# JEMA.net
KiCad netlist of a schematic drawn in EAGLE
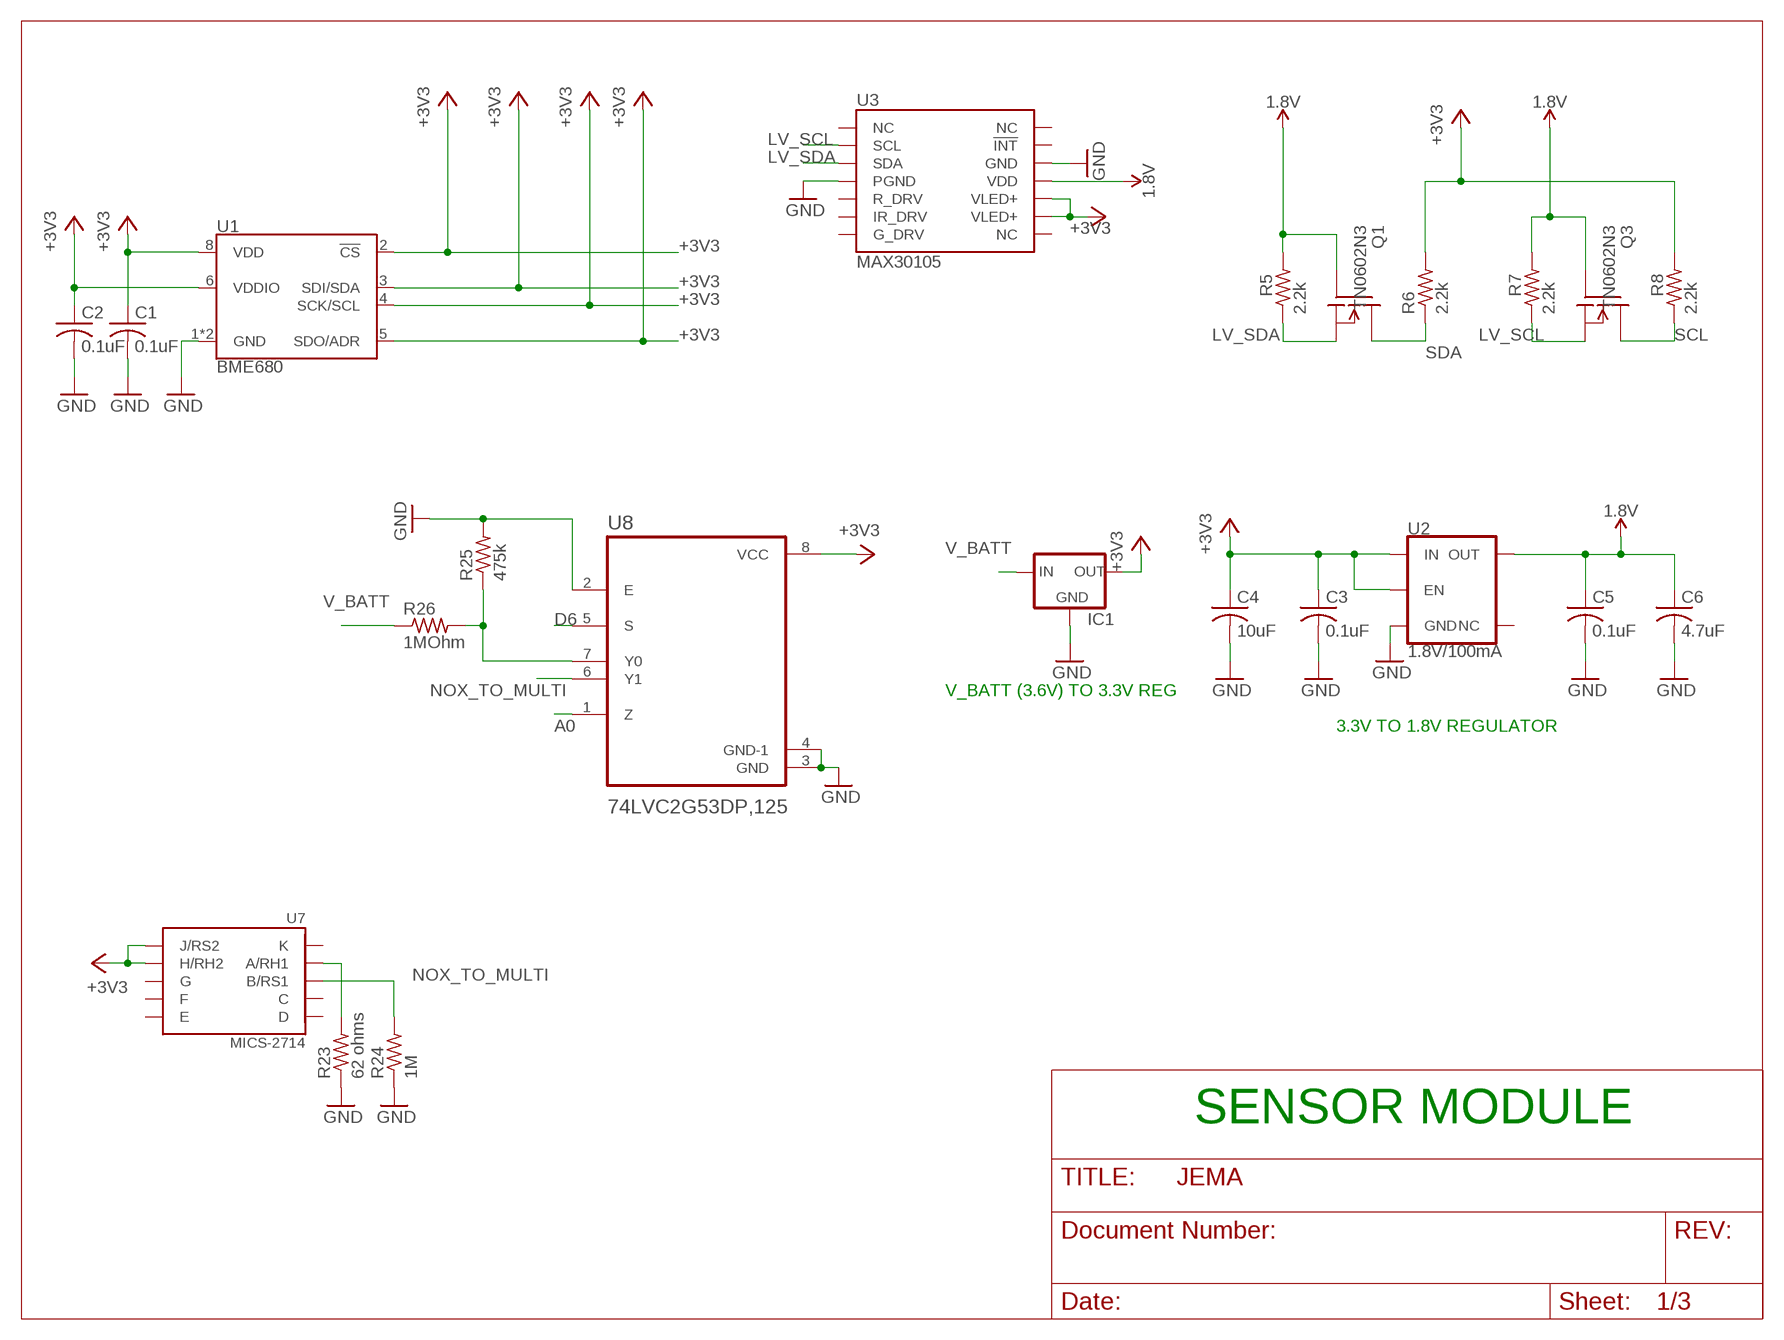
[diagram p0: schematic, sheet 1]
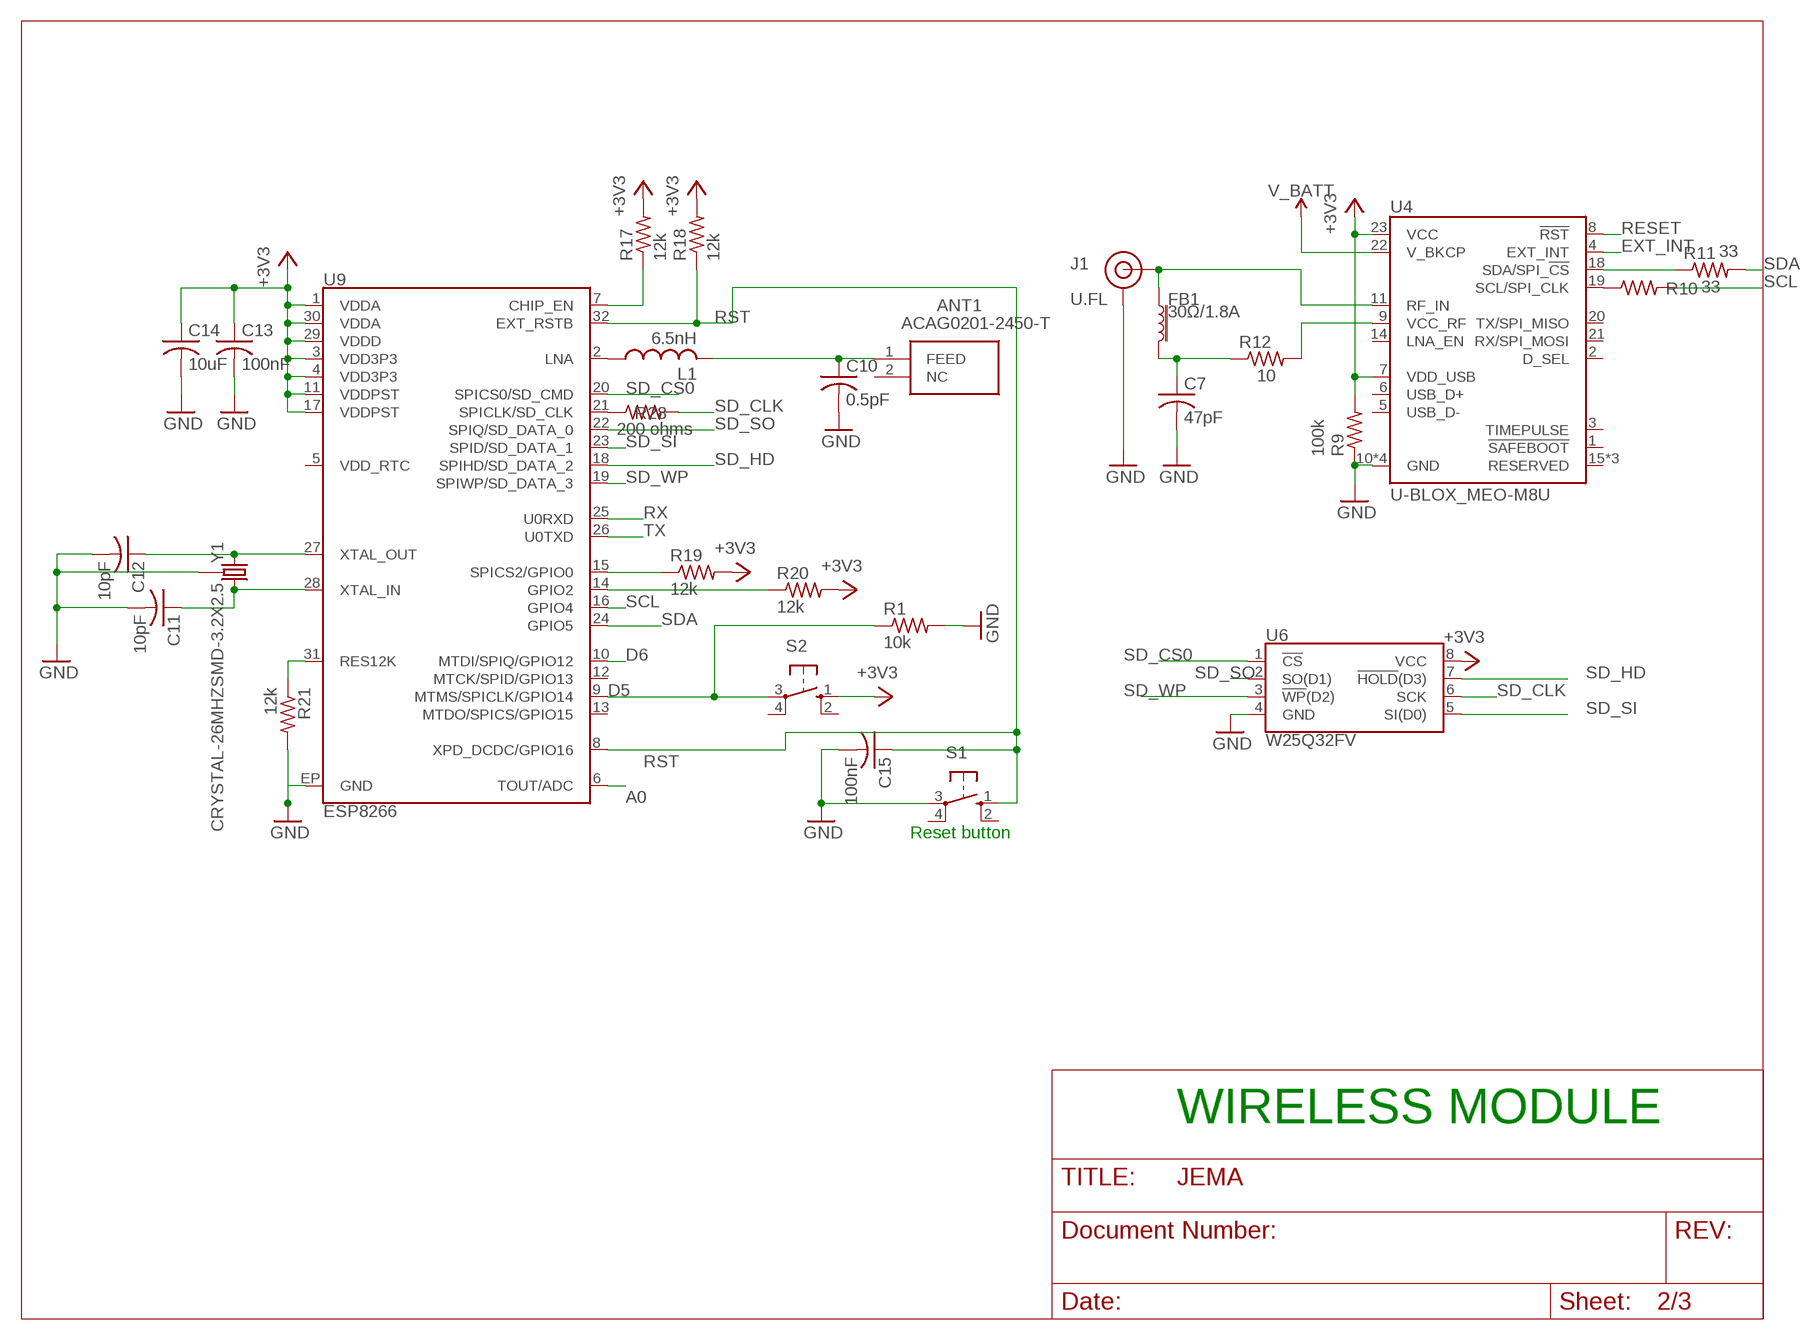
[diagram p1: schematic, sheet 2]
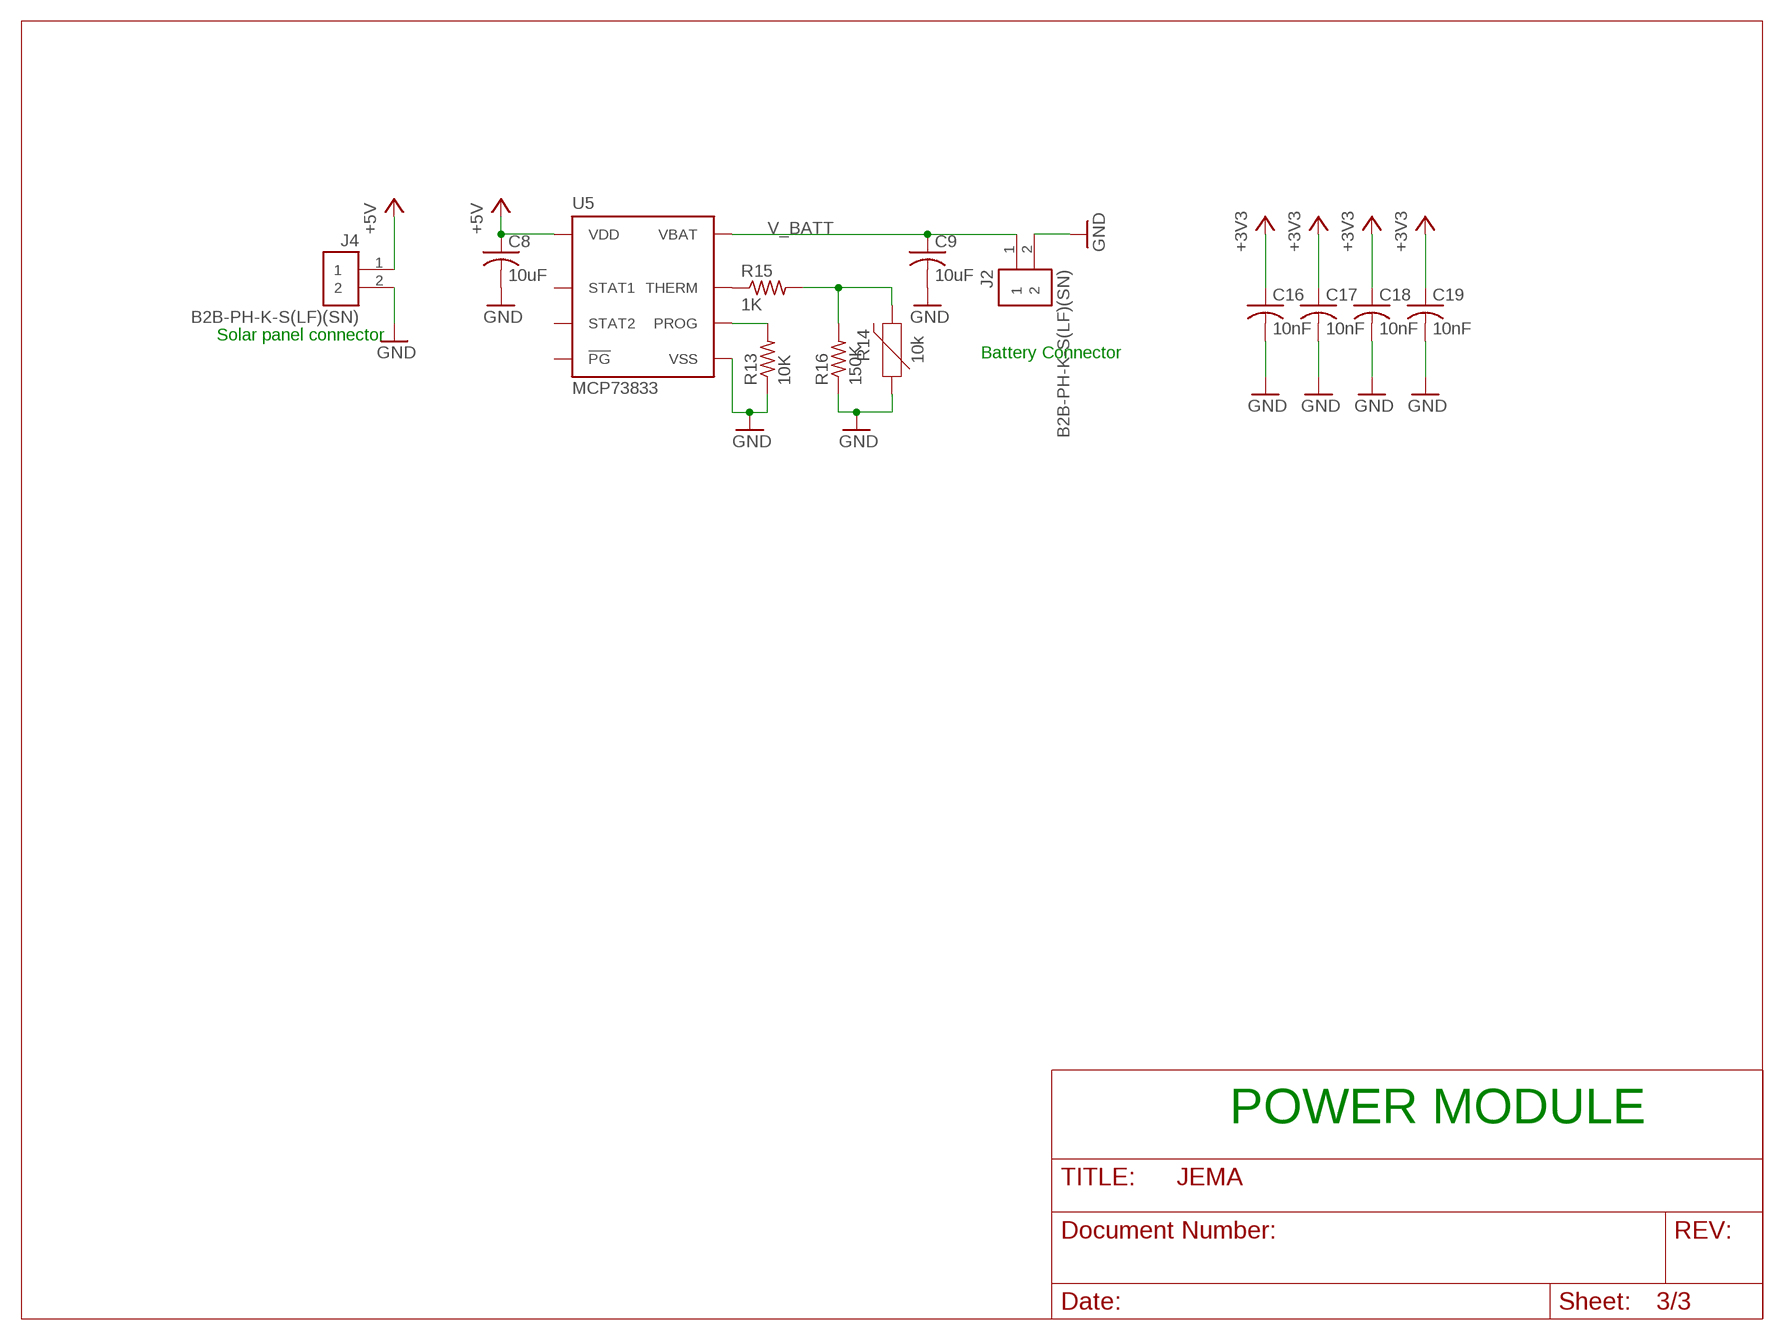
[diagram p2: schematic, sheet 3]

(export (version "E")
  (design (tool "Eeschema 10.0.6"))
  (components
    (comp (ref "C8")
      (value "10uF")
      (footprint "eagle-import:C0805")
      (libsource (lib "eagle-import") (part "C-USC0805"))
    )
    (comp (ref "C9")
      (value "10uF")
      (footprint "eagle-import:C0805")
      (libsource (lib "eagle-import") (part "C-USC0805"))
    )
    (comp (ref "C16")
      (value "10nF")
      (footprint "eagle-import:C0805")
      (libsource (lib "eagle-import") (part "C-USC0805"))
    )
    (comp (ref "C17")
      (value "10nF")
      (footprint "eagle-import:C0805")
      (libsource (lib "eagle-import") (part "C-USC0805"))
    )
    (comp (ref "C18")
      (value "10nF")
      (footprint "eagle-import:C0805")
      (libsource (lib "eagle-import") (part "C-USC0805"))
    )
    (comp (ref "C19")
      (value "10nF")
      (footprint "eagle-import:C0805")
      (libsource (lib "eagle-import") (part "C-USC0805"))
    )
    (comp (ref "J2")
      (value "B2B-PH-K-S(LF)(SN)")
      (footprint "eagle-import:JST_B2B-PH-K-S(LF)(SN)")
      (fields (field (name "MF") "JST Sales"))
      (libsource (lib "eagle-import") (part "B2B-PH-K-S(LF)(SN)"))
    )
    (comp (ref "J4")
      (value "B2B-PH-K-S(LF)(SN)")
      (footprint "eagle-import:JST_B2B-PH-K-S(LF)(SN)")
      (fields (field (name "MF") "JST Sales"))
      (libsource (lib "eagle-import") (part "B2B-PH-K-S(LF)(SN)"))
    )
    (comp (ref "R13")
      (value "10K")
      (footprint "eagle-import:R0805")
      (libsource (lib "eagle-import") (part "R-US_R0805"))
    )
    (comp (ref "R14")
      (value "10k")
      (footprint "eagle-import:0603")
      (libsource (lib "eagle-import") (part "NTC-THERMISTOR-0603"))
    )
    (comp (ref "R15")
      (value "1K")
      (footprint "eagle-import:R0805")
      (libsource (lib "eagle-import") (part "R-US_R0805"))
    )
    (comp (ref "R16")
      (value "150K")
      (footprint "eagle-import:R0805")
      (libsource (lib "eagle-import") (part "R-US_R0805"))
    )
    (comp (ref "U5")
      (value "MCP73833")
      (footprint "eagle-import:DFN-10")
      (libsource (lib "eagle-import") (part "MCP73833"))
    )
    (comp (ref "ANT1")
      (value "ACAG0201-2450-T")
      (footprint "eagle-import:ANTC2012X70N")
      (fields (field (name "MOUSER_PART_NUMBER") "815-G0201-2450-T"))
      (libsource (lib "eagle-import") (part "ACAG0201-2450-T"))
    )
    (comp (ref "C7")
      (value "47pF")
      (footprint "eagle-import:C0805")
      (libsource (lib "eagle-import") (part "C-USC0805"))
    )
    (comp (ref "C10")
      (value "0.5pF")
      (footprint "eagle-import:C0805")
      (libsource (lib "eagle-import") (part "C-USC0805"))
    )
    (comp (ref "C11")
      (value "10pF")
      (footprint "eagle-import:C0805")
      (libsource (lib "eagle-import") (part "C-USC0805"))
    )
    (comp (ref "C12")
      (value "10pF")
      (footprint "eagle-import:C0805")
      (libsource (lib "eagle-import") (part "C-USC0805"))
    )
    (comp (ref "C13")
      (value "100nF")
      (footprint "eagle-import:C0805")
      (libsource (lib "eagle-import") (part "C-USC0805"))
    )
    (comp (ref "C14")
      (value "10uF")
      (footprint "eagle-import:C0805")
      (libsource (lib "eagle-import") (part "C-USC0805"))
    )
    (comp (ref "C15")
      (value "100nF")
      (footprint "eagle-import:C0805")
      (libsource (lib "eagle-import") (part "C-USC0805"))
    )
    (comp (ref "FB1")
      (value "30Ω/1.8A")
      (footprint "eagle-import:0603")
      (libsource (lib "eagle-import") (part "FERRITE_BEAD-0603"))
    )
    (comp (ref "J1")
      (value "U.FL")
      (footprint "eagle-import:U.FL")
      (libsource (lib "eagle-import") (part "U.FL2PIN"))
    )
    (comp (ref "L1")
      (value "6.5nH")
      (footprint "eagle-import:L3225M")
      (libsource (lib "eagle-import") (part "L-USL3225M"))
    )
    (comp (ref "R1")
      (value "10k")
      (footprint "eagle-import:R0805")
      (libsource (lib "eagle-import") (part "R-US_R0805"))
    )
    (comp (ref "R9")
      (value "100k")
      (footprint "eagle-import:R0805")
      (libsource (lib "eagle-import") (part "R-US_R0805"))
    )
    (comp (ref "R10")
      (value "33")
      (footprint "eagle-import:R0805")
      (libsource (lib "eagle-import") (part "R-US_R0805"))
    )
    (comp (ref "R11")
      (value "33")
      (footprint "eagle-import:R0805")
      (libsource (lib "eagle-import") (part "R-US_R0805"))
    )
    (comp (ref "R12")
      (value "10")
      (footprint "eagle-import:R0805")
      (libsource (lib "eagle-import") (part "R-US_R0805"))
    )
    (comp (ref "R17")
      (value "12k")
      (footprint "eagle-import:M0805")
      (libsource (lib "eagle-import") (part "R-US_M0805"))
    )
    (comp (ref "R18")
      (value "12k")
      (footprint "eagle-import:M0805")
      (libsource (lib "eagle-import") (part "R-US_M0805"))
    )
    (comp (ref "R19")
      (value "12k")
      (footprint "eagle-import:M0805")
      (libsource (lib "eagle-import") (part "R-US_M0805"))
    )
    (comp (ref "R20")
      (value "12k")
      (footprint "eagle-import:M0805")
      (libsource (lib "eagle-import") (part "R-US_M0805"))
    )
    (comp (ref "R21")
      (value "12k")
      (footprint "eagle-import:M0805")
      (libsource (lib "eagle-import") (part "R-US_M0805"))
    )
    (comp (ref "R28")
      (value "200 ohms")
      (footprint "eagle-import:R0805")
      (libsource (lib "eagle-import") (part "R-US_R0805"))
    )
    (comp (ref "S1")
      (value "10-XX")
      (footprint "eagle-import:B3F-10XX")
      (fields (field (name "MPN") "B3F-1000"))
      (libsource (lib "eagle-import") (part "10-XX"))
    )
    (comp (ref "S2")
      (value "10-XX")
      (footprint "eagle-import:B3F-10XX")
      (fields (field (name "MPN") "B3F-1000"))
      (libsource (lib "eagle-import") (part "10-XX"))
    )
    (comp (ref "U4")
      (value "U-BLOX_MEO-M8U")
      (footprint "eagle-import:NEO-M9N_M8T_M8U")
      (libsource (lib "eagle-import") (part "U-BLOX_MEO-M8U"))
    )
    (comp (ref "U6")
      (value "W25Q32FV")
      (footprint "eagle-import:SOIC-8")
      (libsource (lib "eagle-import") (part "W25Q32FVSS"))
    )
    (comp (ref "U9")
      (value "ESP8266")
      (footprint "eagle-import:QFN32-5X5MM")
      (libsource (lib "eagle-import") (part "ESP8266"))
    )
    (comp (ref "Y1")
      (value "CRYSTAL-26MHZSMD-3.2X2.5")
      (footprint "eagle-import:CRYSTAL-SMD-3.2X2.5MM")
      (libsource (lib "eagle-import") (part "CRYSTAL-26MHZSMD-3.2X2.5"))
    )
    (comp (ref "C1")
      (value "0.1uF")
      (footprint "eagle-import:C0805")
      (libsource (lib "eagle-import") (part "C-USC0805"))
    )
    (comp (ref "C2")
      (value "0.1uF")
      (footprint "eagle-import:C0805")
      (libsource (lib "eagle-import") (part "C-USC0805"))
    )
    (comp (ref "C3")
      (value "0.1uF")
      (footprint "eagle-import:C0805")
      (libsource (lib "eagle-import") (part "C-USC0805"))
    )
    (comp (ref "C4")
      (value "10uF")
      (footprint "eagle-import:C0805")
      (libsource (lib "eagle-import") (part "C-USC0805"))
    )
    (comp (ref "C5")
      (value "0.1uF")
      (footprint "eagle-import:C0805")
      (libsource (lib "eagle-import") (part "C-USC0805"))
    )
    (comp (ref "C6")
      (value "4.7uF")
      (footprint "eagle-import:C0805")
      (libsource (lib "eagle-import") (part "C-USC0805"))
    )
    (comp (ref "IC1")
      (value "MCP1700TRI")
      (footprint "eagle-import:TO92")
      (libsource (lib "eagle-import") (part "MCP1700TRI"))
    )
    (comp (ref "Q1")
      (value "TN0602N3")
      (footprint "eagle-import:TO-92")
      (libsource (lib "eagle-import") (part "TN0602N3"))
    )
    (comp (ref "Q3")
      (value "TN0602N3")
      (footprint "eagle-import:TO-92")
      (libsource (lib "eagle-import") (part "TN0602N3"))
    )
    (comp (ref "R5")
      (value "2.2k")
      (footprint "eagle-import:R0805")
      (libsource (lib "eagle-import") (part "R-US_R0805"))
    )
    (comp (ref "R6")
      (value "2.2k")
      (footprint "eagle-import:R0805")
      (libsource (lib "eagle-import") (part "R-US_R0805"))
    )
    (comp (ref "R7")
      (value "2.2k")
      (footprint "eagle-import:R0805")
      (libsource (lib "eagle-import") (part "R-US_R0805"))
    )
    (comp (ref "R8")
      (value "2.2k")
      (footprint "eagle-import:R0805")
      (libsource (lib "eagle-import") (part "R-US_R0805"))
    )
    (comp (ref "R23")
      (value "62 ohms")
      (footprint "eagle-import:M0805")
      (libsource (lib "eagle-import") (part "R-US_M0805"))
    )
    (comp (ref "R24")
      (value "1M")
      (footprint "eagle-import:M0805")
      (libsource (lib "eagle-import") (part "R-US_M0805"))
    )
    (comp (ref "R25")
      (value "475k")
      (footprint "eagle-import:M0805")
      (libsource (lib "eagle-import") (part "R-US_M0805"))
    )
    (comp (ref "R26")
      (value "1MOhm")
      (footprint "eagle-import:M0805")
      (libsource (lib "eagle-import") (part "R-US_M0805"))
    )
    (comp (ref "U1")
      (value "BME680")
      (footprint "eagle-import:LGA3.0X3.0")
      (libsource (lib "eagle-import") (part "BME680-LGA"))
    )
    (comp (ref "U2")
      (value "1.8V/100mA")
      (footprint "eagle-import:SC70")
      (libsource (lib "eagle-import") (part "V_REG_SP6214-1.8V"))
    )
    (comp (ref "U3")
      (value "MAX30105")
      (footprint "eagle-import:OLGA-14")
      (libsource (lib "eagle-import") (part "MAX3010X-30105"))
    )
    (comp (ref "U7")
      (value "MICS-2714")
      (footprint "eagle-import:MICS-SMD10")
      (fields (field (name "MF") "SGX Sensortech"))
      (libsource (lib "eagle-import") (part "MICS-2714"))
    )
    (comp (ref "U8")
      (value "74LVC2G53DP,125")
      (footprint "eagle-import:SOP65P490X110-8N")
      (fields (field (name "MF") "Nexperia USA"))
      (libsource (lib "eagle-import") (part "74LVC2G53DP,125"))
    )
  )
  (nets
    (net (code "1") (name "+3V3") (class "Default")
      (node (ref "C1") (pin "1") (pinfunction "1_1") (pintype "passive"))
      (node (ref "C13") (pin "1") (pinfunction "1_1") (pintype "passive"))
      (node (ref "C14") (pin "1") (pinfunction "1_1") (pintype "passive"))
      (node (ref "C16") (pin "1") (pinfunction "1_1") (pintype "passive"))
      (node (ref "C17") (pin "1") (pinfunction "1_1") (pintype "passive"))
      (node (ref "C18") (pin "1") (pinfunction "1_1") (pintype "passive"))
      (node (ref "C19") (pin "1") (pinfunction "1_1") (pintype "passive"))
      (node (ref "C2") (pin "1") (pinfunction "1_1") (pintype "passive"))
      (node (ref "C3") (pin "1") (pinfunction "1_1") (pintype "passive"))
      (node (ref "C4") (pin "1") (pinfunction "1_1") (pintype "passive"))
      (node (ref "IC1") (pin "3") (pinfunction "OUT_3") (pintype "passive"))
      (node (ref "R17") (pin "2") (pinfunction "2_2") (pintype "passive"))
      (node (ref "R18") (pin "2") (pinfunction "2_2") (pintype "passive"))
      (node (ref "R19") (pin "2") (pinfunction "2_2") (pintype "passive"))
      (node (ref "R20") (pin "2") (pinfunction "2_2") (pintype "passive"))
      (node (ref "R6") (pin "2") (pinfunction "2_2") (pintype "passive"))
      (node (ref "R8") (pin "2") (pinfunction "2_2") (pintype "passive"))
      (node (ref "R9") (pin "2") (pinfunction "2_2") (pintype "passive"))
      (node (ref "S2") (pin "1") (pinfunction "S_1") (pintype "passive"))
      (node (ref "U1") (pin "2") (pinfunction "~{CS}_2") (pintype "bidirectional"))
      (node (ref "U1") (pin "3") (pinfunction "SDI/SDA_3") (pintype "bidirectional"))
      (node (ref "U1") (pin "4") (pinfunction "SCK/SCL_4") (pintype "bidirectional"))
      (node (ref "U1") (pin "5") (pinfunction "SDO/ADR_5") (pintype "bidirectional"))
      (node (ref "U1") (pin "6") (pinfunction "VDDIO_6") (pintype "bidirectional"))
      (node (ref "U1") (pin "8") (pinfunction "VDD_8") (pintype "bidirectional"))
      (node (ref "U2") (pin "1") (pinfunction "IN_1") (pintype "input"))
      (node (ref "U2") (pin "3") (pinfunction "EN_3") (pintype "input"))
      (node (ref "U3") (pin "10") (pinfunction "VLED+_10") (pintype "bidirectional"))
      (node (ref "U3") (pin "9") (pinfunction "VLED+_9") (pintype "bidirectional"))
      (node (ref "U4") (pin "23") (pinfunction "VCC_23") (pintype "bidirectional"))
      (node (ref "U4") (pin "7") (pinfunction "VDD_USB_7") (pintype "bidirectional"))
      (node (ref "U6") (pin "8") (pinfunction "VCC_8") (pintype "bidirectional"))
      (node (ref "U7") (pin "H") (pinfunction "H/RH2_H") (pintype "bidirectional"))
      (node (ref "U7") (pin "J") (pinfunction "J/RS2_J") (pintype "bidirectional"))
      (node (ref "U8") (pin "8") (pinfunction "VCC_8") (pintype "power_in"))
      (node (ref "U9") (pin "1") (pinfunction "VDDA_1") (pintype "bidirectional"))
      (node (ref "U9") (pin "11") (pinfunction "VDDPST_11") (pintype "bidirectional"))
      (node (ref "U9") (pin "17") (pinfunction "VDDPST_17") (pintype "bidirectional"))
      (node (ref "U9") (pin "29") (pinfunction "VDDD_29") (pintype "bidirectional"))
      (node (ref "U9") (pin "3") (pinfunction "VDD3P3_3") (pintype "bidirectional"))
      (node (ref "U9") (pin "30") (pinfunction "VDDA_30") (pintype "bidirectional"))
      (node (ref "U9") (pin "4") (pinfunction "VDD3P3_4") (pintype "bidirectional"))
    )
    (net (code "2") (name "+5V") (class "Default")
      (node (ref "C8") (pin "1") (pinfunction "1_1") (pintype "passive"))
      (node (ref "J4") (pin "1") (pinfunction "1_1") (pintype "passive"))
      (node (ref "U5") (pin "P$1") (pinfunction "VDD_P$1") (pintype "bidirectional"))
      (node (ref "U5") (pin "P$2") (pinfunction "VDD_P$2") (pintype "bidirectional"))
    )
    (net (code "3") (name "1.8V") (class "Default")
      (node (ref "C5") (pin "1") (pinfunction "1_1") (pintype "passive"))
      (node (ref "C6") (pin "1") (pinfunction "1_1") (pintype "passive"))
      (node (ref "Q1") (pin "2") (pinfunction "G_2") (pintype "passive"))
      (node (ref "Q3") (pin "2") (pinfunction "G_2") (pintype "passive"))
      (node (ref "R5") (pin "2") (pinfunction "2_2") (pintype "passive"))
      (node (ref "R7") (pin "2") (pinfunction "2_2") (pintype "passive"))
      (node (ref "U2") (pin "5") (pinfunction "OUT_5") (pintype "passive"))
      (node (ref "U3") (pin "11") (pinfunction "VDD_11") (pintype "bidirectional"))
    )
    (net (code "4") (name "A0") (class "Default")
      (node (ref "U8") (pin "1") (pinfunction "Z_1") (pintype "bidirectional"))
      (node (ref "U9") (pin "6") (pinfunction "TOUT/ADC_6") (pintype "bidirectional"))
    )
    (net (code "5") (name "D5") (class "Default")
      (node (ref "R1") (pin "1") (pinfunction "1_1") (pintype "passive"))
      (node (ref "S2") (pin "3") (pinfunction "P_3") (pintype "passive"))
      (node (ref "U9") (pin "9") (pinfunction "MTMS/SPICLK/GPIO14_9") (pintype "bidirectional"))
    )
    (net (code "6") (name "D6") (class "Default")
      (node (ref "U8") (pin "5") (pinfunction "S_5") (pintype "bidirectional"))
      (node (ref "U9") (pin "10") (pinfunction "MTDI/SPIQ/GPIO12_10") (pintype "bidirectional"))
    )
    (net (code "7") (name "EXT_INT") (class "Default")
      (node (ref "U4") (pin "4") (pinfunction "EXT_INT_4") (pintype "bidirectional"))
    )
    (net (code "8") (name "GND") (class "Default")
      (node (ref "C1") (pin "2") (pinfunction "2_2") (pintype "passive"))
      (node (ref "C10") (pin "2") (pinfunction "2_2") (pintype "passive"))
      (node (ref "C11") (pin "2") (pinfunction "2_2") (pintype "passive"))
      (node (ref "C12") (pin "2") (pinfunction "2_2") (pintype "passive"))
      (node (ref "C13") (pin "2") (pinfunction "2_2") (pintype "passive"))
      (node (ref "C14") (pin "2") (pinfunction "2_2") (pintype "passive"))
      (node (ref "C15") (pin "2") (pinfunction "2_2") (pintype "passive"))
      (node (ref "C16") (pin "2") (pinfunction "2_2") (pintype "passive"))
      (node (ref "C17") (pin "2") (pinfunction "2_2") (pintype "passive"))
      (node (ref "C18") (pin "2") (pinfunction "2_2") (pintype "passive"))
      (node (ref "C19") (pin "2") (pinfunction "2_2") (pintype "passive"))
      (node (ref "C2") (pin "2") (pinfunction "2_2") (pintype "passive"))
      (node (ref "C3") (pin "2") (pinfunction "2_2") (pintype "passive"))
      (node (ref "C4") (pin "2") (pinfunction "2_2") (pintype "passive"))
      (node (ref "C5") (pin "2") (pinfunction "2_2") (pintype "passive"))
      (node (ref "C6") (pin "2") (pinfunction "2_2") (pintype "passive"))
      (node (ref "C7") (pin "2") (pinfunction "2_2") (pintype "passive"))
      (node (ref "C8") (pin "2") (pinfunction "2_2") (pintype "passive"))
      (node (ref "C9") (pin "2") (pinfunction "2_2") (pintype "passive"))
      (node (ref "IC1") (pin "1") (pinfunction "GND_1") (pintype "input"))
      (node (ref "J1") (pin "1") (pinfunction "GND_1") (pintype "bidirectional"))
      (node (ref "J1") (pin "2") (pinfunction "GND_2") (pintype "bidirectional"))
      (node (ref "J2") (pin "2") (pinfunction "2_2") (pintype "passive"))
      (node (ref "J4") (pin "2") (pinfunction "2_2") (pintype "passive"))
      (node (ref "R1") (pin "2") (pinfunction "2_2") (pintype "passive"))
      (node (ref "R13") (pin "1") (pinfunction "1_1") (pintype "passive"))
      (node (ref "R14") (pin "1") (pinfunction "1_1") (pintype "bidirectional"))
      (node (ref "R16") (pin "1") (pinfunction "1_1") (pintype "passive"))
      (node (ref "R21") (pin "2") (pinfunction "2_2") (pintype "passive"))
      (node (ref "R23") (pin "1") (pinfunction "1_1") (pintype "passive"))
      (node (ref "R24") (pin "1") (pinfunction "1_1") (pintype "passive"))
      (node (ref "R25") (pin "2") (pinfunction "2_2") (pintype "passive"))
      (node (ref "R9") (pin "1") (pinfunction "1_1") (pintype "passive"))
      (node (ref "S1") (pin "3") (pinfunction "P_3") (pintype "passive"))
      (node (ref "U1") (pin "1") (pinfunction "GND_1") (pintype "bidirectional"))
      (node (ref "U1") (pin "7") (pinfunction "GND_7") (pintype "bidirectional"))
      (node (ref "U2") (pin "2") (pinfunction "GND_2") (pintype "input"))
      (node (ref "U3") (pin "12") (pinfunction "GND_12") (pintype "bidirectional"))
      (node (ref "U3") (pin "4") (pinfunction "PGND_4") (pintype "bidirectional"))
      (node (ref "U4") (pin "10") (pinfunction "GND_10") (pintype "bidirectional"))
      (node (ref "U4") (pin "12") (pinfunction "GND_12") (pintype "bidirectional"))
      (node (ref "U4") (pin "13") (pinfunction "GND_13") (pintype "bidirectional"))
      (node (ref "U4") (pin "24") (pinfunction "GND_24") (pintype "bidirectional"))
      (node (ref "U5") (pin "P$11") (pinfunction "VSS_P$11") (pintype "bidirectional"))
      (node (ref "U5") (pin "P$5") (pinfunction "VSS_P$5") (pintype "bidirectional"))
      (node (ref "U6") (pin "4") (pinfunction "GND_4") (pintype "bidirectional"))
      (node (ref "U8") (pin "2") (pinfunction "E_2") (pintype "bidirectional"))
      (node (ref "U8") (pin "3") (pinfunction "GND_3") (pintype "power_in"))
      (node (ref "U8") (pin "4") (pinfunction "GND-1_4") (pintype "power_in"))
      (node (ref "U9") (pin "EP") (pinfunction "GND_EP") (pintype "bidirectional"))
      (node (ref "Y1") (pin "2") (pinfunction "GND_2") (pintype "power_in"))
      (node (ref "Y1") (pin "4") (pinfunction "GND_4") (pintype "power_in"))
    )
    (net (code "9") (name "LV_SCL") (class "Default")
      (node (ref "Q3") (pin "1") (pinfunction "S_1") (pintype "passive"))
      (node (ref "R7") (pin "1") (pinfunction "1_1") (pintype "passive"))
      (node (ref "U3") (pin "2") (pinfunction "SCL_2") (pintype "bidirectional"))
    )
    (net (code "10") (name "LV_SDA") (class "Default")
      (node (ref "Q1") (pin "1") (pinfunction "S_1") (pintype "passive"))
      (node (ref "R5") (pin "1") (pinfunction "1_1") (pintype "passive"))
      (node (ref "U3") (pin "3") (pinfunction "SDA_3") (pintype "bidirectional"))
    )
    (net (code "11") (name "NOX_TO_MULTI") (class "Default")
      (node (ref "R24") (pin "2") (pinfunction "2_2") (pintype "passive"))
      (node (ref "U7") (pin "B") (pinfunction "B/RS1_B") (pintype "bidirectional"))
      (node (ref "U8") (pin "6") (pinfunction "Y1_6") (pintype "bidirectional"))
    )
    (net (code "12") (name "Net-(ANT1-FEED)") (class "Default")
      (node (ref "ANT1") (pin "1") (pinfunction "FEED_1") (pintype "input"))
      (node (ref "C10") (pin "1") (pinfunction "1_1") (pintype "passive"))
      (node (ref "L1") (pin "2") (pinfunction "2_2") (pintype "passive"))
    )
    (net (code "13") (name "Net-(C7-Pad1)") (class "Default")
      (node (ref "C7") (pin "1") (pinfunction "1_1") (pintype "passive"))
      (node (ref "FB1") (pin "2") (pinfunction "2_2") (pintype "passive"))
      (node (ref "R12") (pin "1") (pinfunction "1_1") (pintype "passive"))
    )
    (net (code "14") (name "Net-(J1-SIGNAL)") (class "Default")
      (node (ref "FB1") (pin "1") (pinfunction "1_1") (pintype "passive"))
      (node (ref "J1") (pin "FEED") (pinfunction "SIGNAL_FEED") (pintype "bidirectional"))
      (node (ref "U4") (pin "11") (pinfunction "RF_IN_11") (pintype "bidirectional"))
    )
    (net (code "15") (name "Net-(R14-Pad2)") (class "Default")
      (node (ref "R14") (pin "2") (pinfunction "2_2") (pintype "bidirectional"))
      (node (ref "R15") (pin "2") (pinfunction "2_2") (pintype "passive"))
      (node (ref "R16") (pin "2") (pinfunction "2_2") (pintype "passive"))
    )
    (net (code "16") (name "Net-(U4-SCL{slash}SPI_CLK)") (class "Default")
      (node (ref "R10") (pin "1") (pinfunction "1_1") (pintype "passive"))
      (node (ref "U4") (pin "19") (pinfunction "SCL/SPI_CLK_19") (pintype "bidirectional"))
    )
    (net (code "17") (name "Net-(U4-SDA{slash}SPI_~{CS})") (class "Default")
      (node (ref "R11") (pin "1") (pinfunction "1_1") (pintype "passive"))
      (node (ref "U4") (pin "18") (pinfunction "SDA/SPI_~{CS}_18") (pintype "bidirectional"))
    )
    (net (code "18") (name "Net-(U4-VCC_RF)") (class "Default")
      (node (ref "R12") (pin "2") (pinfunction "2_2") (pintype "passive"))
      (node (ref "U4") (pin "9") (pinfunction "VCC_RF_9") (pintype "bidirectional"))
    )
    (net (code "19") (name "Net-(U5-PROG)") (class "Default")
      (node (ref "R13") (pin "2") (pinfunction "2_2") (pintype "passive"))
      (node (ref "U5") (pin "P$6") (pinfunction "PROG_P$6") (pintype "bidirectional"))
    )
    (net (code "20") (name "Net-(U5-THERM)") (class "Default")
      (node (ref "R15") (pin "1") (pinfunction "1_1") (pintype "passive"))
      (node (ref "U5") (pin "P$8") (pinfunction "THERM_P$8") (pintype "bidirectional"))
    )
    (net (code "21") (name "Net-(U7-A{slash}RH1)") (class "Default")
      (node (ref "R23") (pin "2") (pinfunction "2_2") (pintype "passive"))
      (node (ref "U7") (pin "A") (pinfunction "A/RH1_A") (pintype "bidirectional"))
    )
    (net (code "22") (name "Net-(U8-Y0)") (class "Default")
      (node (ref "R25") (pin "1") (pinfunction "1_1") (pintype "passive"))
      (node (ref "R26") (pin "2") (pinfunction "2_2") (pintype "passive"))
      (node (ref "U8") (pin "7") (pinfunction "Y0_7") (pintype "bidirectional"))
    )
    (net (code "23") (name "Net-(U9-CHIP_EN)") (class "Default")
      (node (ref "R17") (pin "1") (pinfunction "1_1") (pintype "passive"))
      (node (ref "U9") (pin "7") (pinfunction "CHIP_EN_7") (pintype "bidirectional"))
    )
    (net (code "24") (name "Net-(U9-GPIO2)") (class "Default")
      (node (ref "R20") (pin "1") (pinfunction "1_1") (pintype "passive"))
      (node (ref "U9") (pin "14") (pinfunction "GPIO2_14") (pintype "bidirectional"))
    )
    (net (code "25") (name "Net-(U9-LNA)") (class "Default")
      (node (ref "L1") (pin "1") (pinfunction "1_1") (pintype "passive"))
      (node (ref "U9") (pin "2") (pinfunction "LNA_2") (pintype "bidirectional"))
    )
    (net (code "26") (name "Net-(U9-RES12K)") (class "Default")
      (node (ref "R21") (pin "1") (pinfunction "1_1") (pintype "passive"))
      (node (ref "U9") (pin "31") (pinfunction "RES12K_31") (pintype "bidirectional"))
    )
    (net (code "27") (name "Net-(U9-SPICLK{slash}SD_CLK)") (class "Default")
      (node (ref "R28") (pin "1") (pinfunction "1_1") (pintype "passive"))
      (node (ref "U9") (pin "21") (pinfunction "SPICLK/SD_CLK_21") (pintype "bidirectional"))
    )
    (net (code "28") (name "Net-(U9-SPICS2{slash}GPIO0)") (class "Default")
      (node (ref "R19") (pin "1") (pinfunction "1_1") (pintype "passive"))
      (node (ref "U9") (pin "15") (pinfunction "SPICS2/GPIO0_15") (pintype "bidirectional"))
    )
    (net (code "29") (name "Net-(U9-XTAL_IN)") (class "Default")
      (node (ref "C11") (pin "1") (pinfunction "1_1") (pintype "passive"))
      (node (ref "U9") (pin "28") (pinfunction "XTAL_IN_28") (pintype "bidirectional"))
      (node (ref "Y1") (pin "3") (pinfunction "2_3") (pintype "passive"))
    )
    (net (code "30") (name "Net-(U9-XTAL_OUT)") (class "Default")
      (node (ref "C12") (pin "1") (pinfunction "1_1") (pintype "passive"))
      (node (ref "U9") (pin "27") (pinfunction "XTAL_OUT_27") (pintype "bidirectional"))
      (node (ref "Y1") (pin "1") (pinfunction "1_1") (pintype "passive"))
    )
    (net (code "31") (name "RESET") (class "Default")
      (node (ref "U4") (pin "8") (pinfunction "~{RST}_8") (pintype "bidirectional"))
    )
    (net (code "32") (name "RST") (class "Default")
      (node (ref "C15") (pin "1") (pinfunction "1_1") (pintype "passive"))
      (node (ref "R18") (pin "1") (pinfunction "1_1") (pintype "passive"))
      (node (ref "S1") (pin "1") (pinfunction "S_1") (pintype "passive"))
      (node (ref "U9") (pin "32") (pinfunction "EXT_RSTB_32") (pintype "bidirectional"))
      (node (ref "U9") (pin "8") (pinfunction "XPD_DCDC/GPIO16_8") (pintype "bidirectional"))
    )
    (net (code "33") (name "RX") (class "Default")
      (node (ref "U9") (pin "25") (pinfunction "U0RXD_25") (pintype "bidirectional"))
    )
    (net (code "34") (name "SCL") (class "Default")
      (node (ref "Q3") (pin "3") (pinfunction "D_3") (pintype "passive"))
      (node (ref "R10") (pin "2") (pinfunction "2_2") (pintype "passive"))
      (node (ref "R8") (pin "1") (pinfunction "1_1") (pintype "passive"))
      (node (ref "U9") (pin "16") (pinfunction "GPIO4_16") (pintype "bidirectional"))
    )
    (net (code "35") (name "SDA") (class "Default")
      (node (ref "Q1") (pin "3") (pinfunction "D_3") (pintype "passive"))
      (node (ref "R11") (pin "2") (pinfunction "2_2") (pintype "passive"))
      (node (ref "R6") (pin "1") (pinfunction "1_1") (pintype "passive"))
      (node (ref "U9") (pin "24") (pinfunction "GPIO5_24") (pintype "bidirectional"))
    )
    (net (code "36") (name "SD_CLK") (class "Default")
      (node (ref "R28") (pin "2") (pinfunction "2_2") (pintype "passive"))
      (node (ref "U6") (pin "6") (pinfunction "SCK_6") (pintype "bidirectional"))
    )
    (net (code "37") (name "SD_CS0") (class "Default")
      (node (ref "U6") (pin "1") (pinfunction "~{CS}_1") (pintype "bidirectional"))
      (node (ref "U9") (pin "20") (pinfunction "SPICS0/SD_CMD_20") (pintype "bidirectional"))
    )
    (net (code "38") (name "SD_HD") (class "Default")
      (node (ref "U6") (pin "7") (pinfunction "~{HOLD}(D3)_7") (pintype "bidirectional"))
      (node (ref "U9") (pin "18") (pinfunction "SPIHD/SD_DATA_2_18") (pintype "bidirectional"))
    )
    (net (code "39") (name "SD_SI") (class "Default")
      (node (ref "U6") (pin "5") (pinfunction "SI(D0)_5") (pintype "bidirectional"))
      (node (ref "U9") (pin "23") (pinfunction "SPID/SD_DATA_1_23") (pintype "bidirectional"))
    )
    (net (code "40") (name "SD_SO") (class "Default")
      (node (ref "U6") (pin "2") (pinfunction "SO(D1)_2") (pintype "bidirectional"))
      (node (ref "U9") (pin "22") (pinfunction "SPIQ/SD_DATA_0_22") (pintype "bidirectional"))
    )
    (net (code "41") (name "SD_WP") (class "Default")
      (node (ref "U6") (pin "3") (pinfunction "~{WP}(D2)_3") (pintype "bidirectional"))
      (node (ref "U9") (pin "19") (pinfunction "SPIWP/SD_DATA_3_19") (pintype "bidirectional"))
    )
    (net (code "42") (name "TX") (class "Default")
      (node (ref "U9") (pin "26") (pinfunction "U0TXD_26") (pintype "bidirectional"))
    )
    (net (code "43") (name "V_BATT") (class "Default")
      (node (ref "C9") (pin "1") (pinfunction "1_1") (pintype "passive"))
      (node (ref "IC1") (pin "2") (pinfunction "IN_2") (pintype "input"))
      (node (ref "J2") (pin "1") (pinfunction "1_1") (pintype "passive"))
      (node (ref "R26") (pin "1") (pinfunction "1_1") (pintype "passive"))
      (node (ref "U4") (pin "22") (pinfunction "V_BKCP_22") (pintype "bidirectional"))
      (node (ref "U5") (pin "P$10") (pinfunction "VBAT_P$10") (pintype "bidirectional"))
      (node (ref "U5") (pin "P$9") (pinfunction "VBAT_P$9") (pintype "bidirectional"))
    )
    (net (code "44") (name "unconnected-(ANT1-NC-Pad2)") (class "Default")
      (node (ref "ANT1") (pin "2") (pinfunction "NC_2") (pintype "no_connect"))
    )
    (net (code "45") (name "unconnected-(S1-P1-Pad4)") (class "Default")
      (node (ref "S1") (pin "4") (pinfunction "P1_4") (pintype "passive"))
    )
    (net (code "46") (name "unconnected-(S1-S1-Pad2)") (class "Default")
      (node (ref "S1") (pin "2") (pinfunction "S1_2") (pintype "passive"))
    )
    (net (code "47") (name "unconnected-(S2-P1-Pad4)") (class "Default")
      (node (ref "S2") (pin "4") (pinfunction "P1_4") (pintype "passive"))
    )
    (net (code "48") (name "unconnected-(S2-S1-Pad2)") (class "Default")
      (node (ref "S2") (pin "2") (pinfunction "S1_2") (pintype "passive"))
    )
    (net (code "49") (name "unconnected-(U2-NC-Pad4)") (class "Default")
      (node (ref "U2") (pin "4") (pinfunction "NC_4") (pintype "no_connect"))
    )
    (net (code "50") (name "unconnected-(U3-G_DRV-Pad7)") (class "Default")
      (node (ref "U3") (pin "7") (pinfunction "G_DRV_7") (pintype "bidirectional"))
    )
    (net (code "51") (name "unconnected-(U3-IR_DRV-Pad6)") (class "Default")
      (node (ref "U3") (pin "6") (pinfunction "IR_DRV_6") (pintype "bidirectional"))
    )
    (net (code "52") (name "unconnected-(U3-NC-Pad1)") (class "Default")
      (node (ref "U3") (pin "1") (pinfunction "NC_1") (pintype "bidirectional"))
    )
    (net (code "53") (name "unconnected-(U3-NC-Pad8)") (class "Default")
      (node (ref "U3") (pin "8") (pinfunction "NC_8") (pintype "bidirectional"))
    )
    (net (code "54") (name "unconnected-(U3-NC-Pad14)") (class "Default")
      (node (ref "U3") (pin "14") (pinfunction "NC_14") (pintype "bidirectional"))
    )
    (net (code "55") (name "unconnected-(U3-R_DRV-Pad5)") (class "Default")
      (node (ref "U3") (pin "5") (pinfunction "R_DRV_5") (pintype "bidirectional"))
    )
    (net (code "56") (name "unconnected-(U3-~{INT}-Pad13)") (class "Default")
      (node (ref "U3") (pin "13") (pinfunction "~{INT}_13") (pintype "bidirectional"))
    )
    (net (code "57") (name "unconnected-(U4-D_SEL-Pad2)") (class "Default")
      (node (ref "U4") (pin "2") (pinfunction "D_SEL_2") (pintype "bidirectional"))
    )
    (net (code "58") (name "unconnected-(U4-LNA_EN-Pad14)") (class "Default")
      (node (ref "U4") (pin "14") (pinfunction "LNA_EN_14") (pintype "bidirectional"))
    )
    (net (code "59") (name "unconnected-(U4-RESERVED-Pad15)") (class "Default")
      (node (ref "U4") (pin "15") (pinfunction "RESERVED_15") (pintype "no_connect"))
    )
    (net (code "60") (name "unconnected-(U4-RESERVED-Pad16)") (class "Default")
      (node (ref "U4") (pin "16") (pinfunction "RESERVED_16") (pintype "no_connect"))
    )
    (net (code "61") (name "unconnected-(U4-RESERVED-Pad17)") (class "Default")
      (node (ref "U4") (pin "17") (pinfunction "RESERVED_17") (pintype "no_connect"))
    )
    (net (code "62") (name "unconnected-(U4-RX{slash}SPI_MOSI-Pad21)") (class "Default")
      (node (ref "U4") (pin "21") (pinfunction "RX/SPI_MOSI_21") (pintype "bidirectional"))
    )
    (net (code "63") (name "unconnected-(U4-TIMEPULSE-Pad3)") (class "Default")
      (node (ref "U4") (pin "3") (pinfunction "TIMEPULSE_3") (pintype "bidirectional"))
    )
    (net (code "64") (name "unconnected-(U4-TX{slash}SPI_MISO-Pad20)") (class "Default")
      (node (ref "U4") (pin "20") (pinfunction "TX/SPI_MISO_20") (pintype "bidirectional"))
    )
    (net (code "65") (name "unconnected-(U4-USB_D+-Pad6)") (class "Default")
      (node (ref "U4") (pin "6") (pinfunction "USB_D+_6") (pintype "bidirectional"))
    )
    (net (code "66") (name "unconnected-(U4-USB_D--Pad5)") (class "Default")
      (node (ref "U4") (pin "5") (pinfunction "USB_D-_5") (pintype "bidirectional"))
    )
    (net (code "67") (name "unconnected-(U4-~{SAFEBOOT}-Pad1)") (class "Default")
      (node (ref "U4") (pin "1") (pinfunction "~{SAFEBOOT}_1") (pintype "bidirectional"))
    )
    (net (code "68") (name "unconnected-(U5-STAT1-PadP$3)") (class "Default")
      (node (ref "U5") (pin "P$3") (pinfunction "STAT1_P$3") (pintype "bidirectional"))
    )
    (net (code "69") (name "unconnected-(U5-STAT2-PadP$4)") (class "Default")
      (node (ref "U5") (pin "P$4") (pinfunction "STAT2_P$4") (pintype "bidirectional"))
    )
    (net (code "70") (name "unconnected-(U5-~{PG}-PadP$7)") (class "Default")
      (node (ref "U5") (pin "P$7") (pinfunction "~{PG}_P$7") (pintype "bidirectional"))
    )
    (net (code "71") (name "unconnected-(U7-PadC)") (class "Default")
      (node (ref "U7") (pin "C") (pinfunction "C_C") (pintype "bidirectional"))
    )
    (net (code "72") (name "unconnected-(U7-PadD)") (class "Default")
      (node (ref "U7") (pin "D") (pinfunction "D_D") (pintype "bidirectional"))
    )
    (net (code "73") (name "unconnected-(U7-PadE)") (class "Default")
      (node (ref "U7") (pin "E") (pinfunction "E_E") (pintype "bidirectional"))
    )
    (net (code "74") (name "unconnected-(U7-PadF)") (class "Default")
      (node (ref "U7") (pin "F") (pinfunction "F_F") (pintype "bidirectional"))
    )
    (net (code "75") (name "unconnected-(U7-PadG)") (class "Default")
      (node (ref "U7") (pin "G") (pinfunction "G_G") (pintype "bidirectional"))
    )
    (net (code "76") (name "unconnected-(U7-PadK)") (class "Default")
      (node (ref "U7") (pin "K") (pinfunction "K_K") (pintype "bidirectional"))
    )
    (net (code "77") (name "unconnected-(U9-MTCK{slash}SPID{slash}GPIO13-Pad12)") (class "Default")
      (node (ref "U9") (pin "12") (pinfunction "MTCK/SPID/GPIO13_12") (pintype "bidirectional"))
    )
    (net (code "78") (name "unconnected-(U9-MTDO{slash}SPICS{slash}GPIO15-Pad13)") (class "Default")
      (node (ref "U9") (pin "13") (pinfunction "MTDO/SPICS/GPIO15_13") (pintype "bidirectional"))
    )
    (net (code "79") (name "unconnected-(U9-VDD_RTC-Pad5)") (class "Default")
      (node (ref "U9") (pin "5") (pinfunction "VDD_RTC_5") (pintype "bidirectional"))
    )
  )
)
